# photoboard1.net
KiCad netlist of a schematic drawn in EAGLE
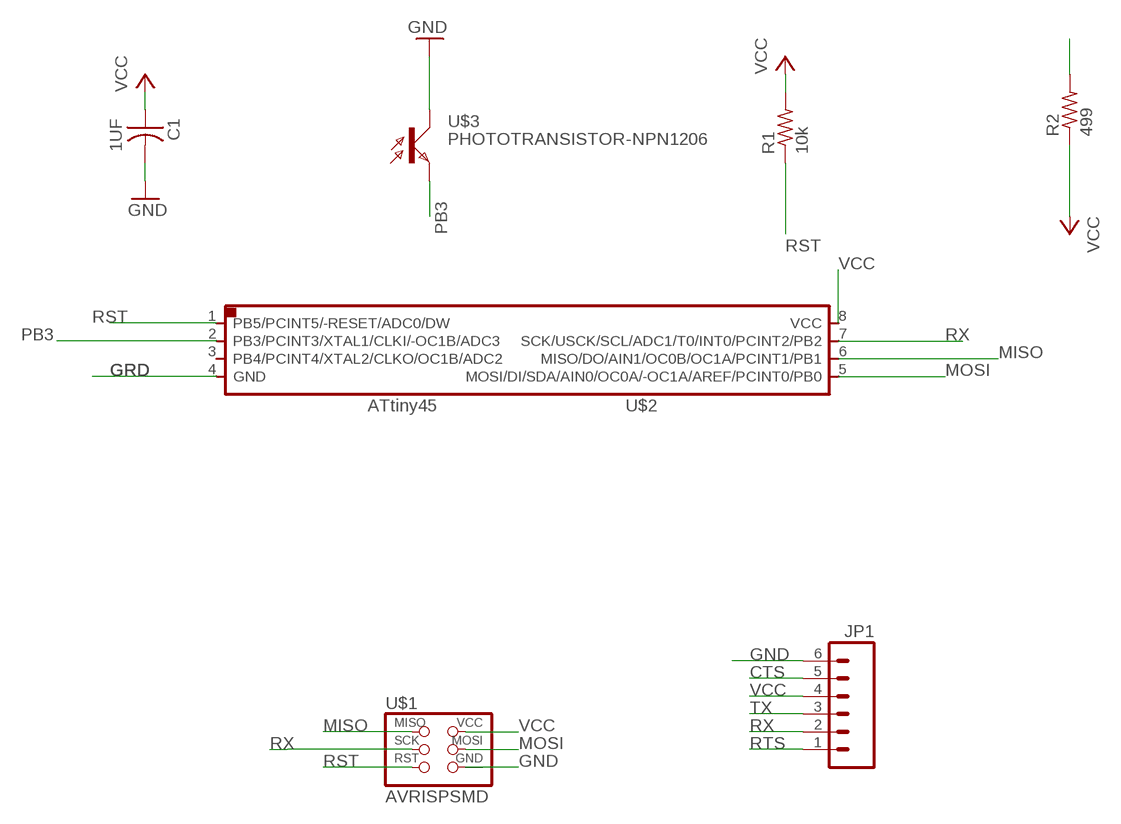
[diagram p0: schematic, sheet 1]

(export (version "E")
  (design (tool "Eeschema 10.0.6"))
  (components
    (comp (ref "C1")
      (value "1UF")
      (footprint "eagle-import:C1206FAB")
      (libsource (lib "eagle-import") (part "CAP-US1206FAB"))
    )
    (comp (ref "JP1")
      (value "M06SMD")
      (footprint "eagle-import:1X06-SMD")
      (libsource (lib "eagle-import") (part "M06SMD"))
    )
    (comp (ref "R1")
      (value "10k")
      (footprint "eagle-import:R1206")
      (libsource (lib "eagle-import") (part "RES-US1206"))
    )
    (comp (ref "R2")
      (value "499")
      (footprint "eagle-import:R1206")
      (libsource (lib "eagle-import") (part "RES-US1206"))
    )
    (comp (ref "U$1")
      (value "AVRISPSMD")
      (footprint "eagle-import:2X03SMD")
      (libsource (lib "eagle-import") (part "AVRISPSMD"))
    )
    (comp (ref "U$2")
      (value "ATTINY45SI")
      (footprint "eagle-import:SOIC8")
      (libsource (lib "eagle-import") (part "ATTINY45SI"))
    )
    (comp (ref "U$3")
      (value "PHOTOTRANSISTOR-NPN1206")
      (footprint "eagle-import:OP1206")
      (libsource (lib "eagle-import") (part "PHOTOTRANSISTOR-NPN1206"))
    )
  )
  (nets
    (net (code "1") (name "/CTS") (class "Default")
      (node (ref "JP1") (pin "5") (pinfunction "5_5") (pintype "passive"))
    )
    (net (code "2") (name "/GRD") (class "Default")
      (node (ref "U$2") (pin "4") (pinfunction "GND_4") (pintype "bidirectional"))
    )
    (net (code "3") (name "/MISO") (class "Default")
      (node (ref "U$1") (pin "1") (pinfunction "MISO_1") (pintype "passive"))
      (node (ref "U$2") (pin "6") (pinfunction "MISO/DO/AIN1/OC0B/OC1A/PCINT1/PB1_6") (pintype "bidirectional"))
    )
    (net (code "4") (name "/MOSI") (class "Default")
      (node (ref "U$1") (pin "4") (pinfunction "MOSI_4") (pintype "passive"))
      (node (ref "U$2") (pin "5") (pinfunction "MOSI/DI/SDA/AIN0/OC0A/-OC1A/AREF/PCINT0/PB0_5") (pintype "bidirectional"))
    )
    (net (code "5") (name "/PB3") (class "Default")
      (node (ref "R2") (pin "2") (pinfunction "2_2") (pintype "passive"))
      (node (ref "U$2") (pin "2") (pinfunction "PB3/PCINT3/XTAL1/CLKI/-OC1B/ADC3_2") (pintype "bidirectional"))
      (node (ref "U$3") (pin "EMITTER") (pinfunction "E_EMITTER") (pintype "passive"))
    )
    (net (code "6") (name "/RST") (class "Default")
      (node (ref "R1") (pin "1") (pinfunction "1_1") (pintype "passive"))
      (node (ref "U$1") (pin "5") (pinfunction "RST_5") (pintype "passive"))
      (node (ref "U$2") (pin "1") (pinfunction "PB5/PCINT5/-RESET/ADC0/DW_1") (pintype "bidirectional"))
    )
    (net (code "7") (name "/RTS") (class "Default")
      (node (ref "JP1") (pin "1") (pinfunction "1_1") (pintype "passive"))
    )
    (net (code "8") (name "/RX") (class "Default")
      (node (ref "JP1") (pin "2") (pinfunction "2_2") (pintype "passive"))
      (node (ref "U$1") (pin "3") (pinfunction "SCK_3") (pintype "passive"))
      (node (ref "U$2") (pin "7") (pinfunction "SCK/USCK/SCL/ADC1/T0/INT0/PCINT2/PB2_7") (pintype "bidirectional"))
    )
    (net (code "9") (name "/TX") (class "Default")
      (node (ref "JP1") (pin "3") (pinfunction "3_3") (pintype "passive"))
    )
    (net (code "10") (name "GND") (class "Default")
      (node (ref "C1") (pin "2") (pinfunction "2_2") (pintype "passive"))
      (node (ref "JP1") (pin "6") (pinfunction "6_6") (pintype "passive"))
      (node (ref "U$1") (pin "6") (pinfunction "GND_6") (pintype "passive"))
      (node (ref "U$3") (pin "COLLECTOR") (pinfunction "C_COLLECTOR") (pintype "passive"))
    )
    (net (code "11") (name "VCC") (class "Default")
      (node (ref "C1") (pin "1") (pinfunction "1_1") (pintype "passive"))
      (node (ref "JP1") (pin "4") (pinfunction "4_4") (pintype "passive"))
      (node (ref "R1") (pin "2") (pinfunction "2_2") (pintype "passive"))
      (node (ref "R2") (pin "1") (pinfunction "1_1") (pintype "passive"))
      (node (ref "U$1") (pin "2") (pinfunction "VCC_2") (pintype "passive"))
      (node (ref "U$2") (pin "8") (pinfunction "VCC_8") (pintype "bidirectional"))
    )
    (net (code "12") (name "unconnected-(U$2-PB4{slash}PCINT4{slash}XTAL2{slash}CLKO{slash}OC1B{slash}ADC2-Pad3)") (class "Default")
      (node (ref "U$2") (pin "3") (pinfunction "PB4/PCINT4/XTAL2/CLKO/OC1B/ADC2_3") (pintype "bidirectional"))
    )
  )
)
